# entropy_king_dk.net
KiCad netlist of a schematic drawn in EAGLE
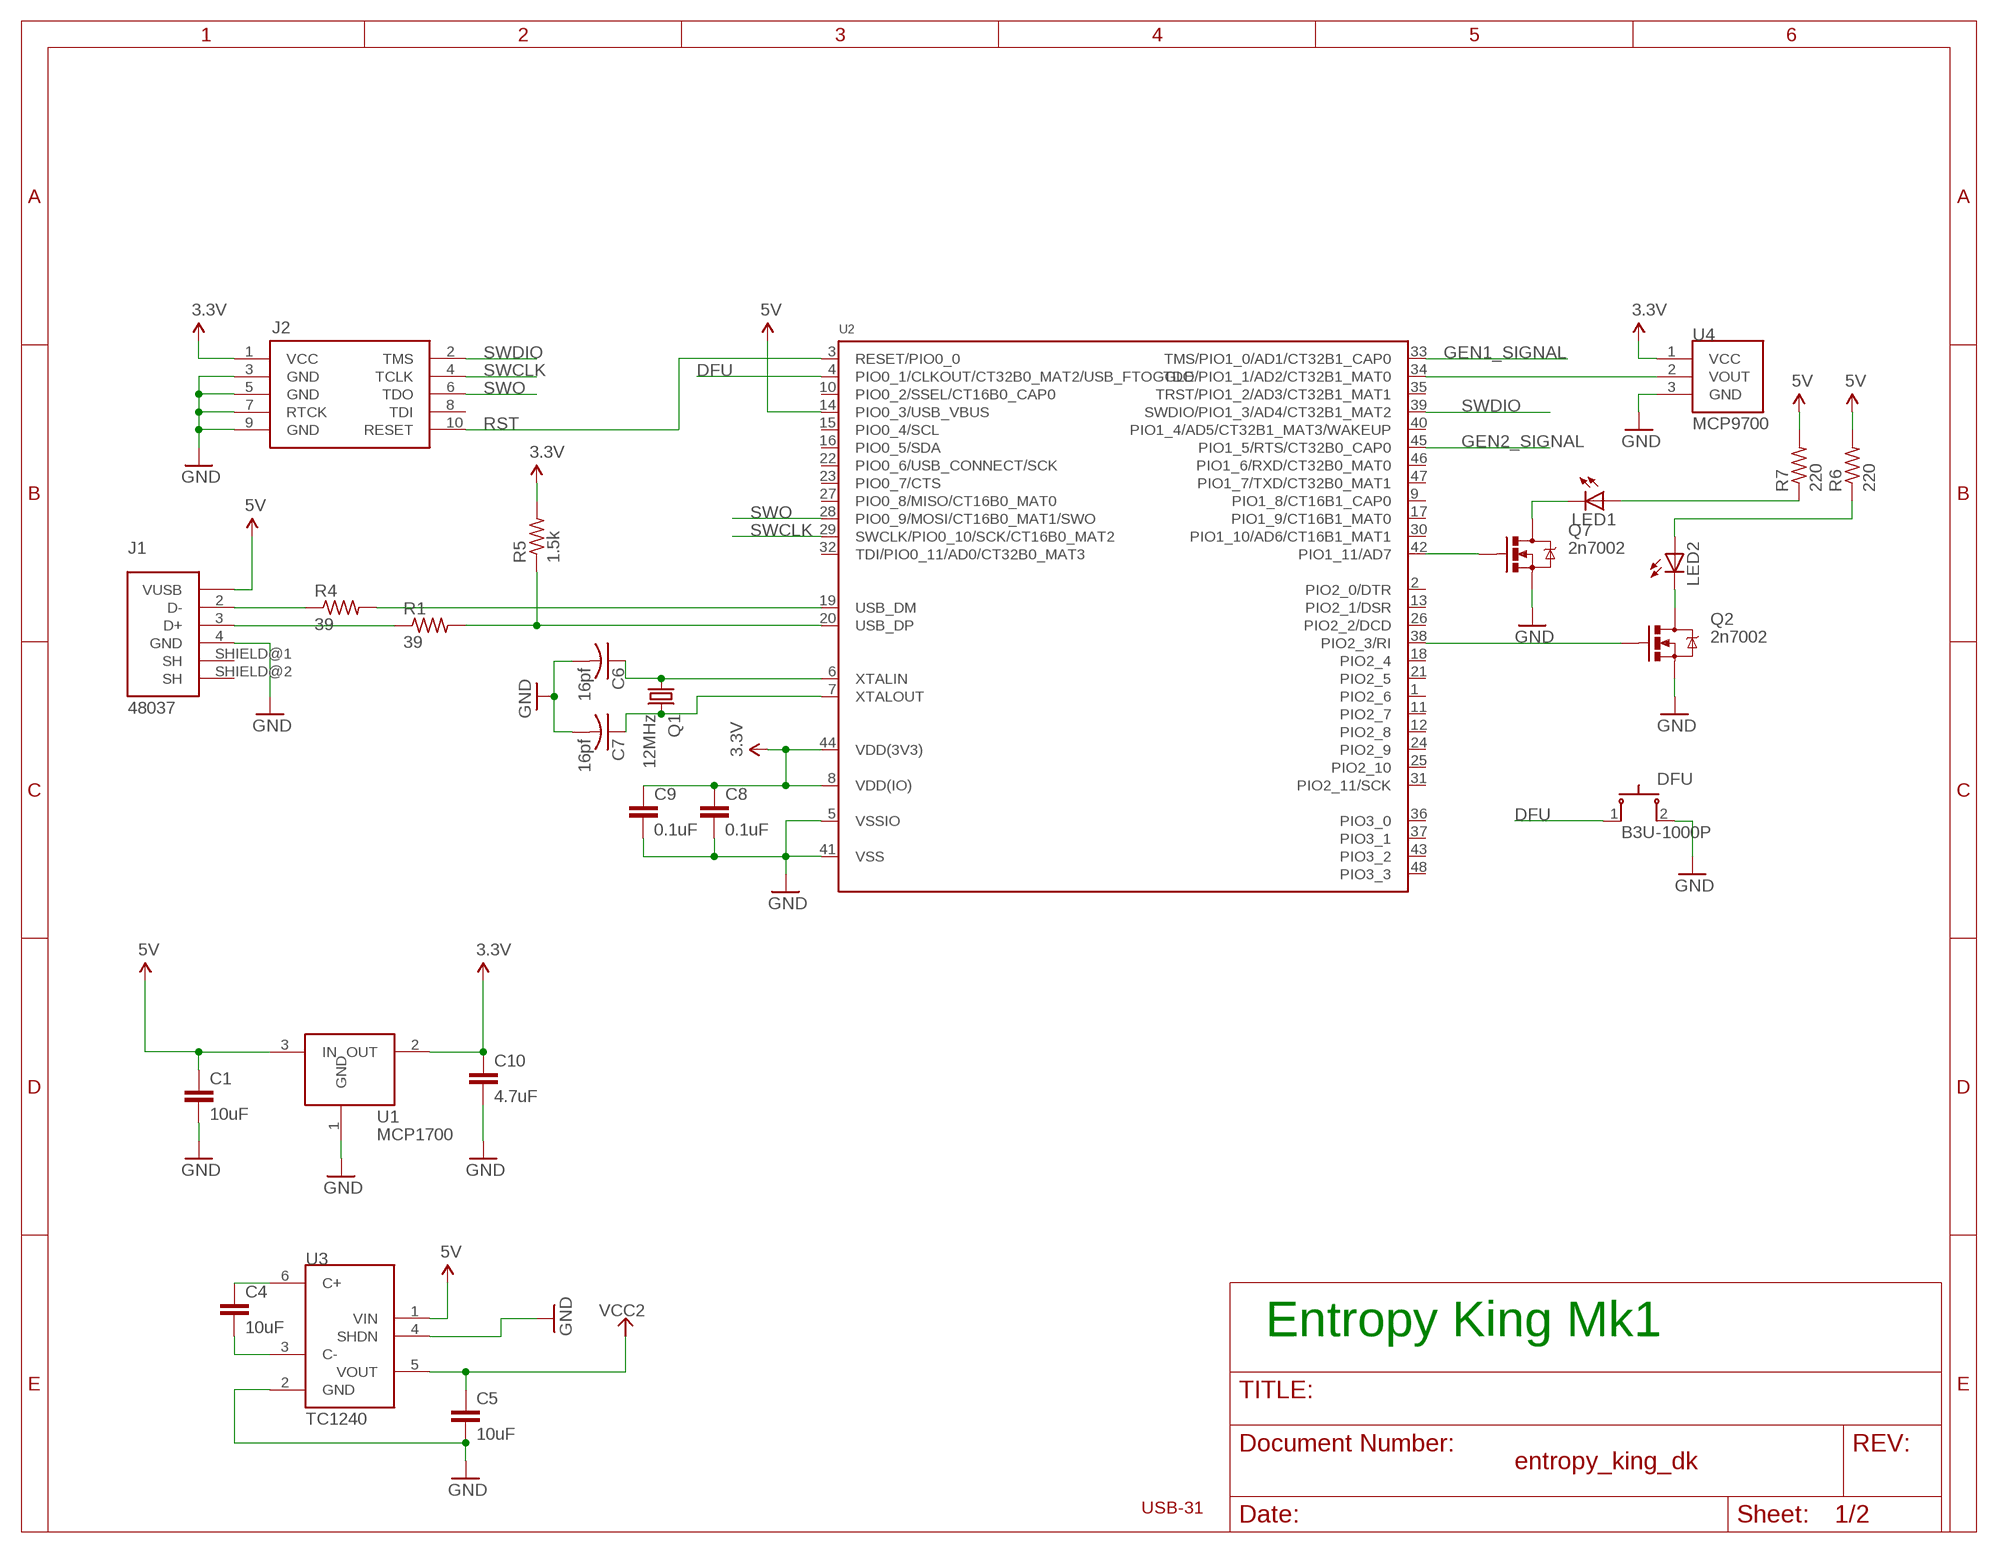
[diagram p0: schematic, sheet 1]
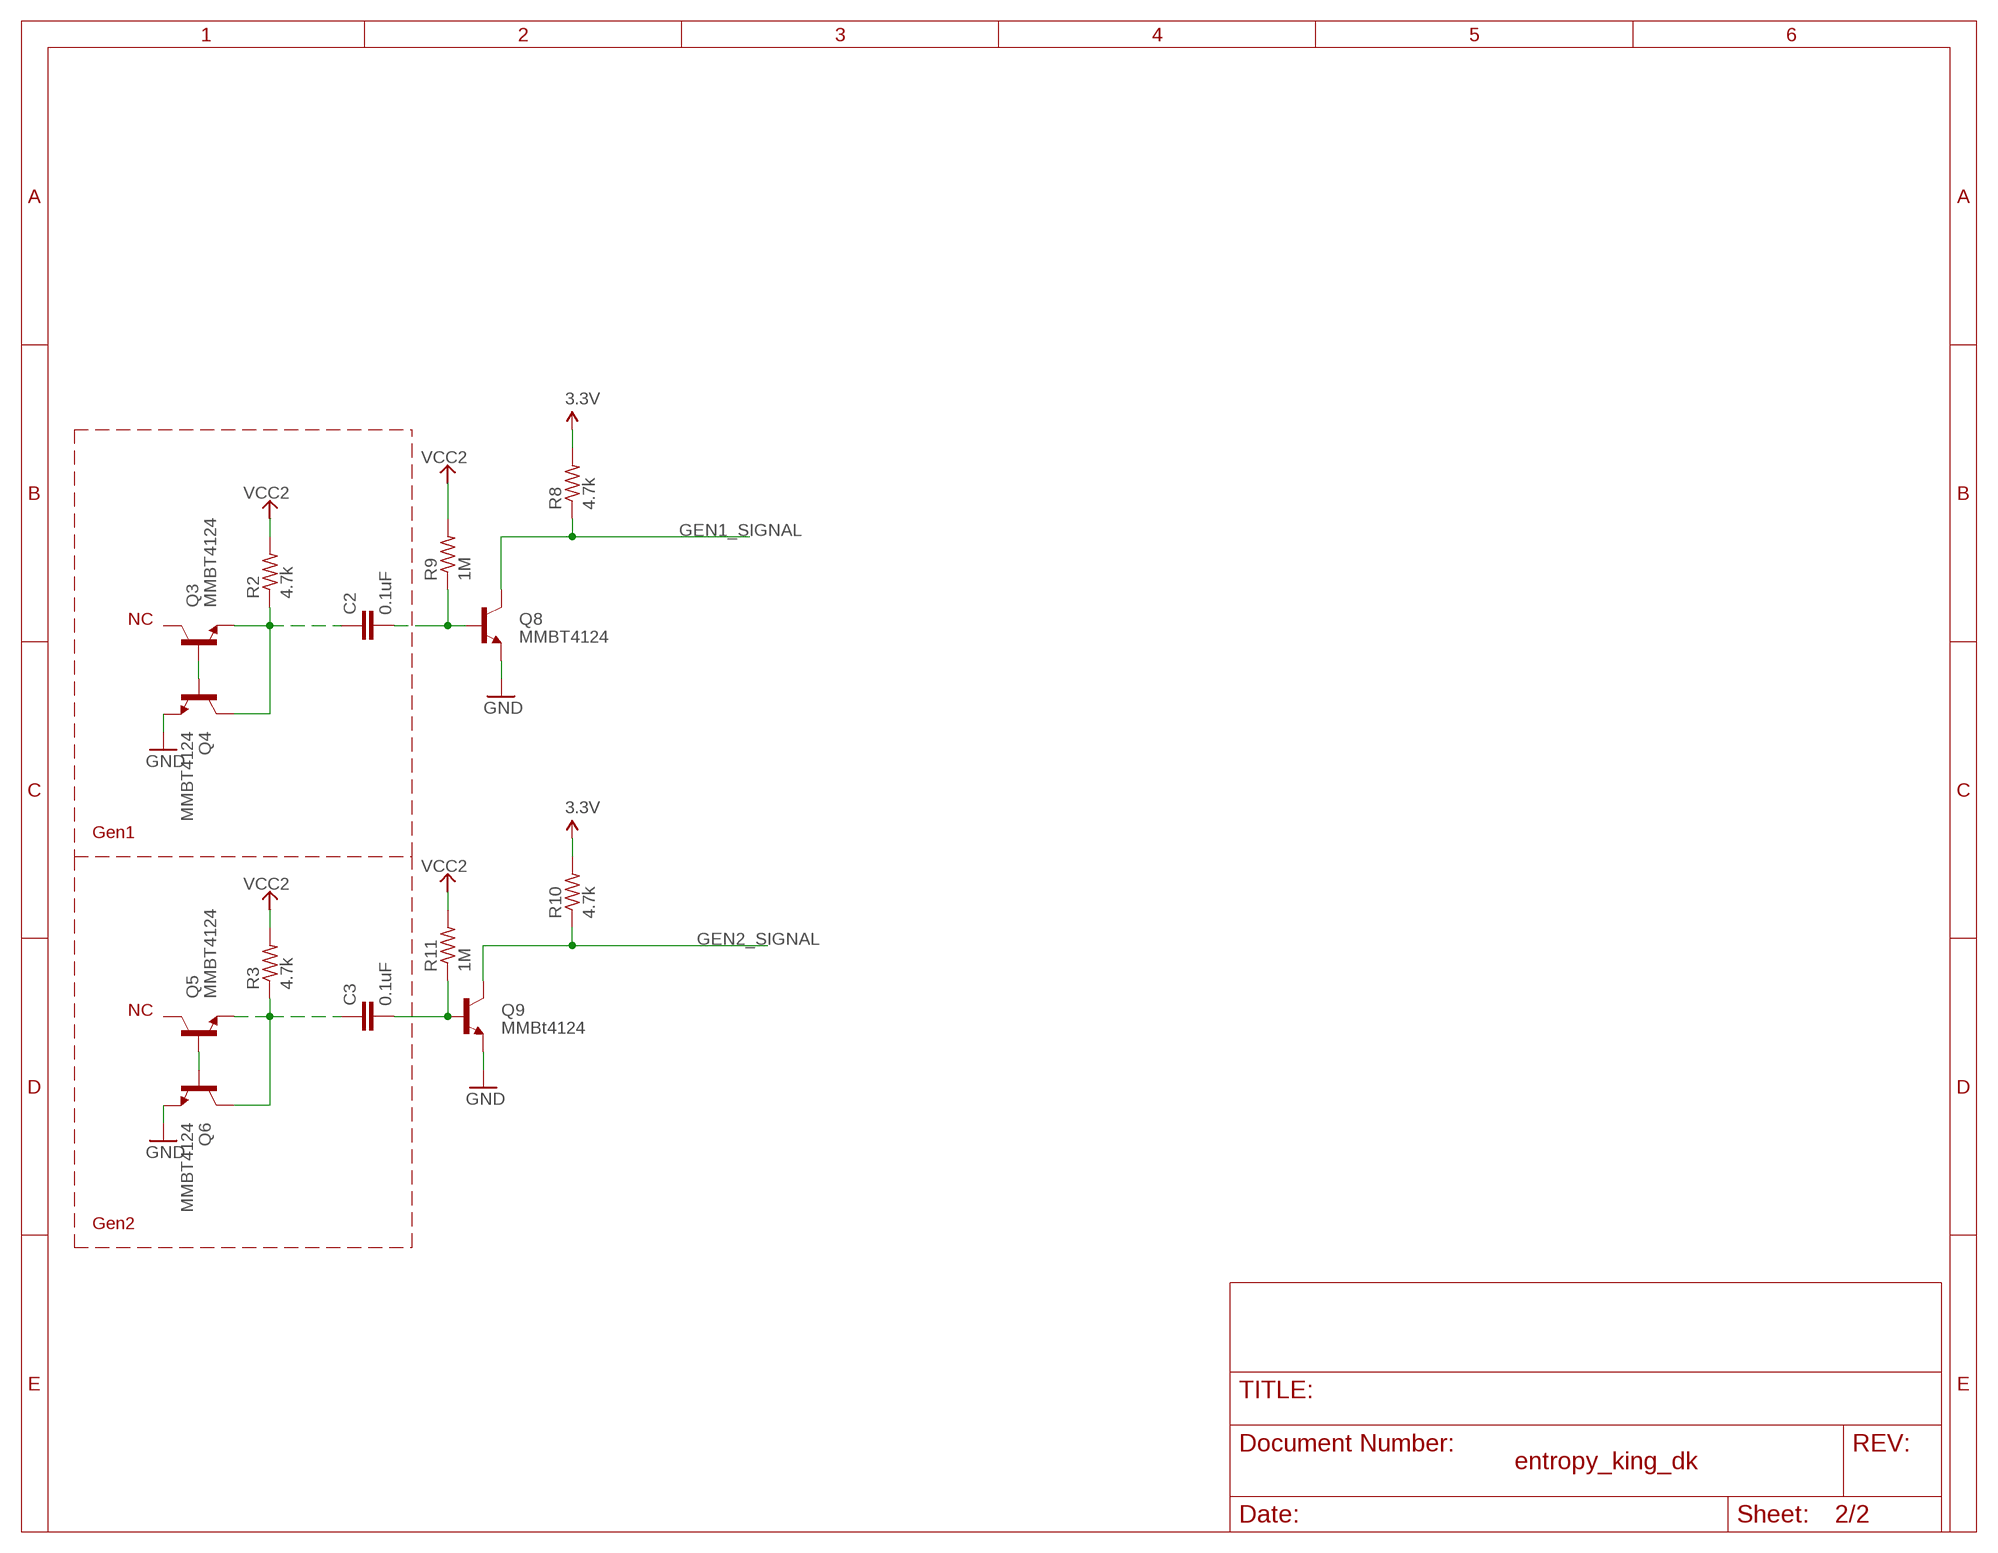
[diagram p1: schematic, sheet 2]

(export (version "E")
  (design (tool "Eeschema 10.0.6"))
  (components
    (comp (ref "C1")
      (value "10uF")
      (footprint "eagle-import:C0805")
      (libsource (lib "eagle-import") (part "C-EUC0805"))
    )
    (comp (ref "C4")
      (value "10uF")
      (footprint "eagle-import:C0805")
      (libsource (lib "eagle-import") (part "C-EUC0805"))
    )
    (comp (ref "C5")
      (value "10uF")
      (footprint "eagle-import:C0805")
      (libsource (lib "eagle-import") (part "C-EUC0805"))
    )
    (comp (ref "C6")
      (value "16pf")
      (footprint "eagle-import:C0603")
      (libsource (lib "eagle-import") (part "C-USC0603"))
    )
    (comp (ref "C7")
      (value "16pf")
      (footprint "eagle-import:C0603")
      (libsource (lib "eagle-import") (part "C-USC0603"))
    )
    (comp (ref "C8")
      (value "0.1uF")
      (footprint "eagle-import:C0603")
      (libsource (lib "eagle-import") (part "C-EUC0603"))
    )
    (comp (ref "C9")
      (value "0.1uF")
      (footprint "eagle-import:C0603")
      (libsource (lib "eagle-import") (part "C-EUC0603"))
    )
    (comp (ref "C10")
      (value "4.7uF")
      (footprint "eagle-import:C0603")
      (libsource (lib "eagle-import") (part "C-EUC0603"))
    )
    (comp (ref "CASE1")
      (value "USB-31")
      (footprint "eagle-import:USB-31")
      (libsource (lib "eagle-import") (part "USB-31"))
    )
    (comp (ref "DFU")
      (value "B3U-1000P")
      (footprint "eagle-import:B3U-1000P")
      (libsource (lib "eagle-import") (part "B3U-1000P"))
    )
    (comp (ref "J1")
      (value "48037")
      (footprint "eagle-import:48037")
      (libsource (lib "eagle-import") (part "48037"))
    )
    (comp (ref "J2")
      (value "ARM_MINI_10PIN_JTAG")
      (footprint "eagle-import:2X05_SMD")
      (libsource (lib "eagle-import") (part "ARM_MINI_10PIN_JTAG"))
    )
    (comp (ref "LED1")
      (value "LED1206")
      (footprint "eagle-import:LED-1206")
      (libsource (lib "eagle-import") (part "LED1206"))
    )
    (comp (ref "LED2")
      (value "LED1206")
      (footprint "eagle-import:LED-1206")
      (libsource (lib "eagle-import") (part "LED1206"))
    )
    (comp (ref "Q1")
      (value "12MHz")
      (footprint "eagle-import:CRYSTAL-SMD-5X3.2")
      (libsource (lib "eagle-import") (part "CRYSTAL25X3.2"))
    )
    (comp (ref "Q2")
      (value "2n7002")
      (footprint "eagle-import:SOT23-3")
      (libsource (lib "eagle-import") (part "MOSFET-NCHANNELSMD"))
    )
    (comp (ref "Q7")
      (value "2n7002")
      (footprint "eagle-import:SOT23-3")
      (libsource (lib "eagle-import") (part "MOSFET-NCHANNELSMD"))
    )
    (comp (ref "R1")
      (value "39")
      (footprint "eagle-import:R0603")
      (libsource (lib "eagle-import") (part "R-US_R0603"))
    )
    (comp (ref "R4")
      (value "39")
      (footprint "eagle-import:R0603")
      (libsource (lib "eagle-import") (part "R-US_R0603"))
    )
    (comp (ref "R5")
      (value "1.5k")
      (footprint "eagle-import:R0603")
      (libsource (lib "eagle-import") (part "R-US_R0603"))
    )
    (comp (ref "R6")
      (value "220")
      (footprint "eagle-import:R0603")
      (libsource (lib "eagle-import") (part "R-US_R0603"))
    )
    (comp (ref "R7")
      (value "220")
      (footprint "eagle-import:R0603")
      (libsource (lib "eagle-import") (part "R-US_R0603"))
    )
    (comp (ref "U1")
      (value "MCP1700")
      (footprint "eagle-import:SOT23")
      (libsource (lib "eagle-import") (part "MCP1700"))
    )
    (comp (ref "U2")
      (value "LPC1343_QFP")
      (footprint "eagle-import:LQFP48")
      (libsource (lib "eagle-import") (part "LPC1343_QFP"))
    )
    (comp (ref "U3")
      (value "TC1240")
      (footprint "eagle-import:SOT23-6L")
      (libsource (lib "eagle-import") (part "TC1240"))
    )
    (comp (ref "U4")
      (value "MCP9700")
      (footprint "eagle-import:SOT23")
      (libsource (lib "eagle-import") (part "MCP9700"))
    )
    (comp (ref "C2")
      (value "0.1uF")
      (footprint "eagle-import:C0603")
      (libsource (lib "eagle-import") (part "C-EUC0603"))
    )
    (comp (ref "C3")
      (value "0.1uF")
      (footprint "eagle-import:C0603")
      (libsource (lib "eagle-import") (part "C-EUC0603"))
    )
    (comp (ref "Q3")
      (value "MMBT4124")
      (footprint "eagle-import:SOT23-3")
      (libsource (lib "eagle-import") (part "TRANSISTOR_NPNSOT23-3"))
    )
    (comp (ref "Q4")
      (value "MMBT4124")
      (footprint "eagle-import:SOT23-3")
      (libsource (lib "eagle-import") (part "TRANSISTOR_NPNSOT23-3"))
    )
    (comp (ref "Q5")
      (value "MMBT4124")
      (footprint "eagle-import:SOT23-3")
      (libsource (lib "eagle-import") (part "TRANSISTOR_NPNSOT23-3"))
    )
    (comp (ref "Q6")
      (value "MMBT4124")
      (footprint "eagle-import:SOT23-3")
      (libsource (lib "eagle-import") (part "TRANSISTOR_NPNSOT23-3"))
    )
    (comp (ref "Q8")
      (value "MMBT4124")
      (footprint "eagle-import:SOT23-3")
      (libsource (lib "eagle-import") (part "TRANSISTOR_NPNSOT23-3"))
    )
    (comp (ref "Q9")
      (value "MMBt4124")
      (footprint "eagle-import:SOT23-3")
      (libsource (lib "eagle-import") (part "TRANSISTOR_NPNSOT23-3"))
    )
    (comp (ref "R2")
      (value "4.7k")
      (footprint "eagle-import:R0603")
      (libsource (lib "eagle-import") (part "R-US_R0603"))
    )
    (comp (ref "R3")
      (value "4.7k")
      (footprint "eagle-import:R0603")
      (libsource (lib "eagle-import") (part "R-US_R0603"))
    )
    (comp (ref "R8")
      (value "4.7k")
      (footprint "eagle-import:R0603")
      (libsource (lib "eagle-import") (part "R-US_R0603"))
    )
    (comp (ref "R9")
      (value "1M")
      (footprint "eagle-import:R0603")
      (libsource (lib "eagle-import") (part "R-US_R0603"))
    )
    (comp (ref "R10")
      (value "4.7k")
      (footprint "eagle-import:R0603")
      (libsource (lib "eagle-import") (part "R-US_R0603"))
    )
    (comp (ref "R11")
      (value "1M")
      (footprint "eagle-import:R0603")
      (libsource (lib "eagle-import") (part "R-US_R0603"))
    )
  )
  (nets
    (net (code "1") (name "3.3V") (class "Default")
      (node (ref "C10") (pin "1") (pinfunction "1_1") (pintype "passive"))
      (node (ref "C8") (pin "1") (pinfunction "1_1") (pintype "passive"))
      (node (ref "C9") (pin "1") (pinfunction "1_1") (pintype "passive"))
      (node (ref "J2") (pin "1") (pinfunction "VCC_1") (pintype "bidirectional"))
      (node (ref "R10") (pin "2") (pinfunction "2_2") (pintype "passive"))
      (node (ref "R5") (pin "2") (pinfunction "2_2") (pintype "passive"))
      (node (ref "R8") (pin "2") (pinfunction "2_2") (pintype "passive"))
      (node (ref "U1") (pin "2") (pinfunction "OUT_2") (pintype "bidirectional"))
      (node (ref "U2") (pin "44") (pinfunction "VDD(3V3)_44") (pintype "power_in"))
      (node (ref "U2") (pin "8") (pinfunction "VDD(IO)_8") (pintype "power_in"))
      (node (ref "U4") (pin "1") (pinfunction "VCC_1") (pintype "bidirectional"))
    )
    (net (code "2") (name "5V") (class "Default")
      (node (ref "C1") (pin "1") (pinfunction "1_1") (pintype "passive"))
      (node (ref "J1") (pin "1") (pinfunction "VUSB_1") (pintype "bidirectional"))
      (node (ref "R6") (pin "2") (pinfunction "2_2") (pintype "passive"))
      (node (ref "R7") (pin "2") (pinfunction "2_2") (pintype "passive"))
      (node (ref "U1") (pin "3") (pinfunction "IN_3") (pintype "bidirectional"))
      (node (ref "U2") (pin "14") (pinfunction "PIO0_3/USB_VBUS_14") (pintype "bidirectional"))
      (node (ref "U3") (pin "1") (pinfunction "VIN_1") (pintype "bidirectional"))
    )
    (net (code "3") (name "DFU") (class "Default")
      (node (ref "DFU") (pin "1") (pinfunction "1_1") (pintype "bidirectional"))
      (node (ref "U2") (pin "4") (pinfunction "PIO0_1/CLKOUT/CT32B0_MAT2/USB_FTOGGLE_4") (pintype "bidirectional"))
    )
    (net (code "4") (name "GEN1_SIGNAL") (class "Default")
      (node (ref "Q8") (pin "3") (pinfunction "C_3") (pintype "passive"))
      (node (ref "R8") (pin "1") (pinfunction "1_1") (pintype "passive"))
      (node (ref "U2") (pin "33") (pinfunction "TMS/PIO1_0/AD1/CT32B1_CAP0_33") (pintype "bidirectional"))
    )
    (net (code "5") (name "GEN2_SIGNAL") (class "Default")
      (node (ref "Q9") (pin "3") (pinfunction "C_3") (pintype "passive"))
      (node (ref "R10") (pin "1") (pinfunction "1_1") (pintype "passive"))
      (node (ref "U2") (pin "45") (pinfunction "PIO1_5/RTS/CT32B0_CAP0_45") (pintype "bidirectional"))
    )
    (net (code "6") (name "GND") (class "Default")
      (node (ref "C1") (pin "2") (pinfunction "2_2") (pintype "passive"))
      (node (ref "C10") (pin "2") (pinfunction "2_2") (pintype "passive"))
      (node (ref "C5") (pin "2") (pinfunction "2_2") (pintype "passive"))
      (node (ref "C6") (pin "2") (pinfunction "2_2") (pintype "passive"))
      (node (ref "C7") (pin "2") (pinfunction "2_2") (pintype "passive"))
      (node (ref "C8") (pin "2") (pinfunction "2_2") (pintype "passive"))
      (node (ref "C9") (pin "2") (pinfunction "2_2") (pintype "passive"))
      (node (ref "DFU") (pin "2") (pinfunction "2_2") (pintype "bidirectional"))
      (node (ref "J1") (pin "4") (pinfunction "GND_4") (pintype "bidirectional"))
      (node (ref "J2") (pin "3") (pinfunction "GND_3") (pintype "bidirectional"))
      (node (ref "J2") (pin "5") (pinfunction "GND_5") (pintype "bidirectional"))
      (node (ref "J2") (pin "7") (pinfunction "RTCK_7") (pintype "bidirectional"))
      (node (ref "J2") (pin "9") (pinfunction "GND_9") (pintype "bidirectional"))
      (node (ref "Q2") (pin "2") (pinfunction "S_2") (pintype "passive"))
      (node (ref "Q4") (pin "2") (pinfunction "E_2") (pintype "passive"))
      (node (ref "Q6") (pin "2") (pinfunction "E_2") (pintype "passive"))
      (node (ref "Q7") (pin "2") (pinfunction "S_2") (pintype "passive"))
      (node (ref "Q8") (pin "2") (pinfunction "E_2") (pintype "passive"))
      (node (ref "Q9") (pin "2") (pinfunction "E_2") (pintype "passive"))
      (node (ref "U1") (pin "1") (pinfunction "GND_1") (pintype "bidirectional"))
      (node (ref "U2") (pin "41") (pinfunction "VSS_41") (pintype "power_in"))
      (node (ref "U2") (pin "5") (pinfunction "VSSIO_5") (pintype "power_in"))
      (node (ref "U3") (pin "2") (pinfunction "GND_2") (pintype "bidirectional"))
      (node (ref "U3") (pin "4") (pinfunction "SHDN_4") (pintype "bidirectional"))
      (node (ref "U4") (pin "3") (pinfunction "GND_3") (pintype "bidirectional"))
    )
    (net (code "7") (name "Net-(J1-D+)") (class "Default")
      (node (ref "J1") (pin "3") (pinfunction "D+_3") (pintype "bidirectional"))
      (node (ref "R1") (pin "1") (pinfunction "1_1") (pintype "passive"))
    )
    (net (code "8") (name "Net-(J1-D-)") (class "Default")
      (node (ref "J1") (pin "2") (pinfunction "D-_2") (pintype "bidirectional"))
      (node (ref "R4") (pin "1") (pinfunction "1_1") (pintype "passive"))
    )
    (net (code "9") (name "Net-(LED1-PadA)") (class "Default")
      (node (ref "LED1") (pin "A") (pinfunction "A_A") (pintype "passive"))
      (node (ref "R7") (pin "1") (pinfunction "1_1") (pintype "passive"))
    )
    (net (code "10") (name "Net-(LED2-PadA)") (class "Default")
      (node (ref "LED2") (pin "A") (pinfunction "A_A") (pintype "passive"))
      (node (ref "R6") (pin "1") (pinfunction "1_1") (pintype "passive"))
    )
    (net (code "11") (name "Net-(Q1-2)") (class "Default")
      (node (ref "C7") (pin "1") (pinfunction "1_1") (pintype "passive"))
      (node (ref "Q1") (pin "3") (pinfunction "2_3") (pintype "passive"))
      (node (ref "U2") (pin "7") (pinfunction "XTALOUT_7") (pintype "output"))
    )
    (net (code "12") (name "Net-(Q2-D)") (class "Default")
      (node (ref "LED2") (pin "C") (pinfunction "C_C") (pintype "passive"))
      (node (ref "Q2") (pin "3") (pinfunction "D_3") (pintype "passive"))
    )
    (net (code "13") (name "Net-(Q2-G)") (class "Default")
      (node (ref "Q2") (pin "1") (pinfunction "G_1") (pintype "passive"))
      (node (ref "U2") (pin "38") (pinfunction "PIO2_3/RI_38") (pintype "bidirectional"))
    )
    (net (code "14") (name "Net-(Q3-B)") (class "Default")
      (node (ref "Q3") (pin "1") (pinfunction "B_1") (pintype "passive"))
      (node (ref "Q4") (pin "1") (pinfunction "B_1") (pintype "passive"))
    )
    (net (code "15") (name "Net-(Q3-E)") (class "Default")
      (node (ref "C2") (pin "1") (pinfunction "1_1") (pintype "passive"))
      (node (ref "Q3") (pin "2") (pinfunction "E_2") (pintype "passive"))
      (node (ref "Q4") (pin "3") (pinfunction "C_3") (pintype "passive"))
      (node (ref "R2") (pin "1") (pinfunction "1_1") (pintype "passive"))
    )
    (net (code "16") (name "Net-(Q5-B)") (class "Default")
      (node (ref "Q5") (pin "1") (pinfunction "B_1") (pintype "passive"))
      (node (ref "Q6") (pin "1") (pinfunction "B_1") (pintype "passive"))
    )
    (net (code "17") (name "Net-(Q5-E)") (class "Default")
      (node (ref "C3") (pin "1") (pinfunction "1_1") (pintype "passive"))
      (node (ref "Q5") (pin "2") (pinfunction "E_2") (pintype "passive"))
      (node (ref "Q6") (pin "3") (pinfunction "C_3") (pintype "passive"))
      (node (ref "R3") (pin "1") (pinfunction "1_1") (pintype "passive"))
    )
    (net (code "18") (name "Net-(Q7-D)") (class "Default")
      (node (ref "LED1") (pin "C") (pinfunction "C_C") (pintype "passive"))
      (node (ref "Q7") (pin "3") (pinfunction "D_3") (pintype "passive"))
    )
    (net (code "19") (name "Net-(Q7-G)") (class "Default")
      (node (ref "Q7") (pin "1") (pinfunction "G_1") (pintype "passive"))
      (node (ref "U2") (pin "42") (pinfunction "PIO1_11/AD7_42") (pintype "bidirectional"))
    )
    (net (code "20") (name "Net-(Q8-B)") (class "Default")
      (node (ref "C2") (pin "2") (pinfunction "2_2") (pintype "passive"))
      (node (ref "Q8") (pin "1") (pinfunction "B_1") (pintype "passive"))
      (node (ref "R9") (pin "1") (pinfunction "1_1") (pintype "passive"))
    )
    (net (code "21") (name "Net-(Q9-B)") (class "Default")
      (node (ref "C3") (pin "2") (pinfunction "2_2") (pintype "passive"))
      (node (ref "Q9") (pin "1") (pinfunction "B_1") (pintype "passive"))
      (node (ref "R11") (pin "1") (pinfunction "1_1") (pintype "passive"))
    )
    (net (code "22") (name "Net-(U2-TDO{slash}PIO1_1{slash}AD2{slash}CT32B1_MAT0)") (class "Default")
      (node (ref "U2") (pin "34") (pinfunction "TDO/PIO1_1/AD2/CT32B1_MAT0_34") (pintype "bidirectional"))
      (node (ref "U4") (pin "2") (pinfunction "VOUT_2") (pintype "bidirectional"))
    )
    (net (code "23") (name "Net-(U2-USB_DM)") (class "Default")
      (node (ref "R4") (pin "2") (pinfunction "2_2") (pintype "passive"))
      (node (ref "U2") (pin "19") (pinfunction "USB_DM_19") (pintype "bidirectional"))
    )
    (net (code "24") (name "Net-(U2-USB_DP)") (class "Default")
      (node (ref "R1") (pin "2") (pinfunction "2_2") (pintype "passive"))
      (node (ref "R5") (pin "1") (pinfunction "1_1") (pintype "passive"))
      (node (ref "U2") (pin "20") (pinfunction "USB_DP_20") (pintype "bidirectional"))
    )
    (net (code "25") (name "Net-(U2-XTALIN)") (class "Default")
      (node (ref "C6") (pin "1") (pinfunction "1_1") (pintype "passive"))
      (node (ref "Q1") (pin "1") (pinfunction "1_1") (pintype "passive"))
      (node (ref "U2") (pin "6") (pinfunction "XTALIN_6") (pintype "input"))
    )
    (net (code "26") (name "Net-(U3-C+)") (class "Default")
      (node (ref "C4") (pin "1") (pinfunction "1_1") (pintype "passive"))
      (node (ref "U3") (pin "6") (pinfunction "C+_6") (pintype "bidirectional"))
    )
    (net (code "27") (name "Net-(U3-C-)") (class "Default")
      (node (ref "C4") (pin "2") (pinfunction "2_2") (pintype "passive"))
      (node (ref "U3") (pin "3") (pinfunction "C-_3") (pintype "bidirectional"))
    )
    (net (code "28") (name "RST") (class "Default")
      (node (ref "J2") (pin "10") (pinfunction "RESET_10") (pintype "bidirectional"))
      (node (ref "U2") (pin "3") (pinfunction "RESET/PIO0_0_3") (pintype "bidirectional"))
    )
    (net (code "29") (name "SWCLK") (class "Default")
      (node (ref "J2") (pin "4") (pinfunction "TCLK_4") (pintype "bidirectional"))
      (node (ref "U2") (pin "29") (pinfunction "SWCLK/PIO0_10/SCK/CT16B0_MAT2_29") (pintype "bidirectional"))
    )
    (net (code "30") (name "SWDIO") (class "Default")
      (node (ref "J2") (pin "2") (pinfunction "TMS_2") (pintype "bidirectional"))
      (node (ref "U2") (pin "39") (pinfunction "SWDIO/PIO1_3/AD4/CT32B1_MAT2_39") (pintype "bidirectional"))
    )
    (net (code "31") (name "SWO") (class "Default")
      (node (ref "J2") (pin "6") (pinfunction "TDO_6") (pintype "bidirectional"))
      (node (ref "U2") (pin "28") (pinfunction "PIO0_9/MOSI/CT16B0_MAT1/SWO_28") (pintype "bidirectional"))
    )
    (net (code "32") (name "VCC2") (class "Default")
      (node (ref "C5") (pin "1") (pinfunction "1_1") (pintype "passive"))
      (node (ref "R11") (pin "2") (pinfunction "2_2") (pintype "passive"))
      (node (ref "R2") (pin "2") (pinfunction "2_2") (pintype "passive"))
      (node (ref "R3") (pin "2") (pinfunction "2_2") (pintype "passive"))
      (node (ref "R9") (pin "2") (pinfunction "2_2") (pintype "passive"))
      (node (ref "U3") (pin "5") (pinfunction "VOUT_5") (pintype "bidirectional"))
    )
    (net (code "33") (name "unconnected-(J1-SH-PadSHIELD@1)") (class "Default")
      (node (ref "J1") (pin "SHIELD@1") (pinfunction "SH_SHIELD@1") (pintype "bidirectional"))
    )
    (net (code "34") (name "unconnected-(J1-SH-PadSHIELD@2)") (class "Default")
      (node (ref "J1") (pin "SHIELD@2") (pinfunction "SH_SHIELD@2") (pintype "bidirectional"))
    )
    (net (code "35") (name "unconnected-(J2-TDI-Pad8)") (class "Default")
      (node (ref "J2") (pin "8") (pinfunction "TDI_8") (pintype "bidirectional"))
    )
    (net (code "36") (name "unconnected-(Q3-C-Pad3)") (class "Default")
      (node (ref "Q3") (pin "3") (pinfunction "C_3") (pintype "passive"))
    )
    (net (code "37") (name "unconnected-(Q5-C-Pad3)") (class "Default")
      (node (ref "Q5") (pin "3") (pinfunction "C_3") (pintype "passive"))
    )
    (net (code "38") (name "unconnected-(U2-PIO0_2{slash}SSEL{slash}CT16B0_CAP0-Pad10)") (class "Default")
      (node (ref "U2") (pin "10") (pinfunction "PIO0_2/SSEL/CT16B0_CAP0_10") (pintype "bidirectional"))
    )
    (net (code "39") (name "unconnected-(U2-PIO0_4{slash}SCL-Pad15)") (class "Default")
      (node (ref "U2") (pin "15") (pinfunction "PIO0_4/SCL_15") (pintype "bidirectional"))
    )
    (net (code "40") (name "unconnected-(U2-PIO0_5{slash}SDA-Pad16)") (class "Default")
      (node (ref "U2") (pin "16") (pinfunction "PIO0_5/SDA_16") (pintype "bidirectional"))
    )
    (net (code "41") (name "unconnected-(U2-PIO0_6{slash}USB_CONNECT{slash}SCK-Pad22)") (class "Default")
      (node (ref "U2") (pin "22") (pinfunction "PIO0_6/USB_CONNECT/SCK_22") (pintype "bidirectional"))
    )
    (net (code "42") (name "unconnected-(U2-PIO0_7{slash}CTS-Pad23)") (class "Default")
      (node (ref "U2") (pin "23") (pinfunction "PIO0_7/CTS_23") (pintype "bidirectional"))
    )
    (net (code "43") (name "unconnected-(U2-PIO0_8{slash}MISO{slash}CT16B0_MAT0-Pad27)") (class "Default")
      (node (ref "U2") (pin "27") (pinfunction "PIO0_8/MISO/CT16B0_MAT0_27") (pintype "bidirectional"))
    )
    (net (code "44") (name "unconnected-(U2-PIO1_4{slash}AD5{slash}CT32B1_MAT3{slash}WAKEUP-Pad40)") (class "Default")
      (node (ref "U2") (pin "40") (pinfunction "PIO1_4/AD5/CT32B1_MAT3/WAKEUP_40") (pintype "bidirectional"))
    )
    (net (code "45") (name "unconnected-(U2-PIO1_6{slash}RXD{slash}CT32B0_MAT0-Pad46)") (class "Default")
      (node (ref "U2") (pin "46") (pinfunction "PIO1_6/RXD/CT32B0_MAT0_46") (pintype "bidirectional"))
    )
    (net (code "46") (name "unconnected-(U2-PIO1_7{slash}TXD{slash}CT32B0_MAT1-Pad47)") (class "Default")
      (node (ref "U2") (pin "47") (pinfunction "PIO1_7/TXD/CT32B0_MAT1_47") (pintype "bidirectional"))
    )
    (net (code "47") (name "unconnected-(U2-PIO1_8{slash}CT16B1_CAP0-Pad9)") (class "Default")
      (node (ref "U2") (pin "9") (pinfunction "PIO1_8/CT16B1_CAP0_9") (pintype "bidirectional"))
    )
    (net (code "48") (name "unconnected-(U2-PIO1_9{slash}CT16B1_MAT0-Pad17)") (class "Default")
      (node (ref "U2") (pin "17") (pinfunction "PIO1_9/CT16B1_MAT0_17") (pintype "bidirectional"))
    )
    (net (code "49") (name "unconnected-(U2-PIO1_10{slash}AD6{slash}CT16B1_MAT1-Pad30)") (class "Default")
      (node (ref "U2") (pin "30") (pinfunction "PIO1_10/AD6/CT16B1_MAT1_30") (pintype "bidirectional"))
    )
    (net (code "50") (name "unconnected-(U2-PIO2_0{slash}DTR-Pad2)") (class "Default")
      (node (ref "U2") (pin "2") (pinfunction "PIO2_0/DTR_2") (pintype "bidirectional"))
    )
    (net (code "51") (name "unconnected-(U2-PIO2_1{slash}DSR-Pad13)") (class "Default")
      (node (ref "U2") (pin "13") (pinfunction "PIO2_1/DSR_13") (pintype "bidirectional"))
    )
    (net (code "52") (name "unconnected-(U2-PIO2_2{slash}DCD-Pad26)") (class "Default")
      (node (ref "U2") (pin "26") (pinfunction "PIO2_2/DCD_26") (pintype "bidirectional"))
    )
    (net (code "53") (name "unconnected-(U2-PIO2_4-Pad18)") (class "Default")
      (node (ref "U2") (pin "18") (pinfunction "PIO2_4_18") (pintype "bidirectional"))
    )
    (net (code "54") (name "unconnected-(U2-PIO2_5-Pad21)") (class "Default")
      (node (ref "U2") (pin "21") (pinfunction "PIO2_5_21") (pintype "bidirectional"))
    )
    (net (code "55") (name "unconnected-(U2-PIO2_6-Pad1)") (class "Default")
      (node (ref "U2") (pin "1") (pinfunction "PIO2_6_1") (pintype "bidirectional"))
    )
    (net (code "56") (name "unconnected-(U2-PIO2_7-Pad11)") (class "Default")
      (node (ref "U2") (pin "11") (pinfunction "PIO2_7_11") (pintype "bidirectional"))
    )
    (net (code "57") (name "unconnected-(U2-PIO2_8-Pad12)") (class "Default")
      (node (ref "U2") (pin "12") (pinfunction "PIO2_8_12") (pintype "bidirectional"))
    )
    (net (code "58") (name "unconnected-(U2-PIO2_9-Pad24)") (class "Default")
      (node (ref "U2") (pin "24") (pinfunction "PIO2_9_24") (pintype "bidirectional"))
    )
    (net (code "59") (name "unconnected-(U2-PIO2_10-Pad25)") (class "Default")
      (node (ref "U2") (pin "25") (pinfunction "PIO2_10_25") (pintype "bidirectional"))
    )
    (net (code "60") (name "unconnected-(U2-PIO2_11{slash}SCK-Pad31)") (class "Default")
      (node (ref "U2") (pin "31") (pinfunction "PIO2_11/SCK_31") (pintype "bidirectional"))
    )
    (net (code "61") (name "unconnected-(U2-PIO3_0-Pad36)") (class "Default")
      (node (ref "U2") (pin "36") (pinfunction "PIO3_0_36") (pintype "bidirectional"))
    )
    (net (code "62") (name "unconnected-(U2-PIO3_1-Pad37)") (class "Default")
      (node (ref "U2") (pin "37") (pinfunction "PIO3_1_37") (pintype "bidirectional"))
    )
    (net (code "63") (name "unconnected-(U2-PIO3_2-Pad43)") (class "Default")
      (node (ref "U2") (pin "43") (pinfunction "PIO3_2_43") (pintype "bidirectional"))
    )
    (net (code "64") (name "unconnected-(U2-PIO3_3-Pad48)") (class "Default")
      (node (ref "U2") (pin "48") (pinfunction "PIO3_3_48") (pintype "bidirectional"))
    )
    (net (code "65") (name "unconnected-(U2-TDI{slash}PIO0_11{slash}AD0{slash}CT32B0_MAT3-Pad32)") (class "Default")
      (node (ref "U2") (pin "32") (pinfunction "TDI/PIO0_11/AD0/CT32B0_MAT3_32") (pintype "bidirectional"))
    )
    (net (code "66") (name "unconnected-(U2-TRST{slash}PIO1_2{slash}AD3{slash}CT32B1_MAT1-Pad35)") (class "Default")
      (node (ref "U2") (pin "35") (pinfunction "TRST/PIO1_2/AD3/CT32B1_MAT1_35") (pintype "bidirectional"))
    )
  )
)
